# 12-DEBUG_JTAG.net
KiCad netlist of a schematic drawn in Altium Designer
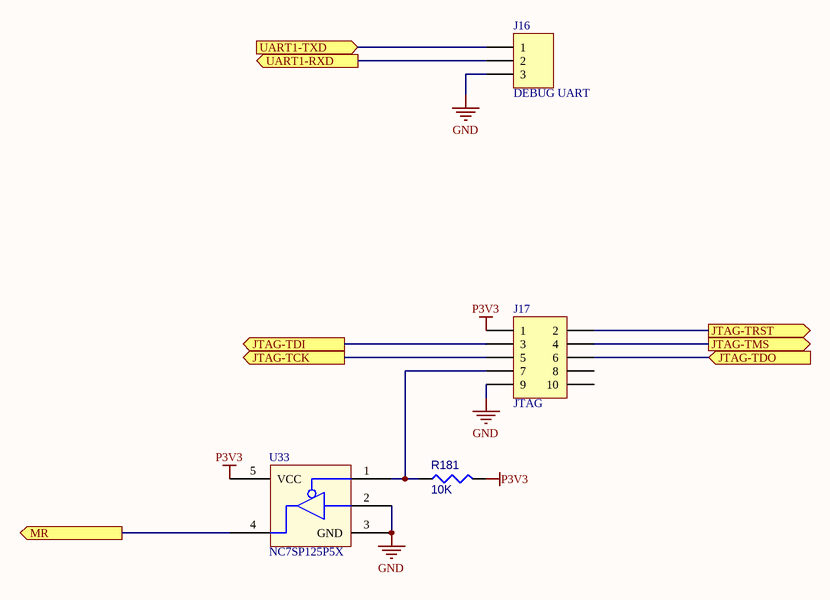
[diagram p0: 12-DEBUG_JTAG.SchDoc]

(export (version "E")
  (design (tool "Eeschema 10.0.6"))
  (components
    (comp (ref "J16")
      (value "DEBUG UART")
      (footprint "HDR1X3")
      (description "Header, 3-Pin")
      (fields (field (name "PUBLISHER") "Altium Limited"))
      (libsource (lib "Miscellaneous Connectors") (part "Header 3"))
    )
    (comp (ref "J17")
      (value "JTAG")
      (footprint "HDR2X5")
      (description "Header, 5-Pin, Dual row")
      (fields (field (name "PUBLISHER") "Altium Limited"))
      (libsource (lib "Miscellaneous Connectors") (part "Header 5X2"))
    )
    (comp (ref "R181") (value "10K") (footprint "0402") (libsource (lib "*") (part "P_R")))
    (comp (ref "U33")
      (value "NC7SP125P5X")
      (footprint "SC70")
      (libsource (lib "Schlib") (part "NC7SP125P5X"))
    )
  )
  (nets
    (net (code "1") (name "/JTAG-TCK") (class "Default")
      (node (ref "J17") (pin "5") (pinfunction "5_5") (pintype "passive"))
    )
    (net (code "2") (name "/JTAG-TDI") (class "Default")
      (node (ref "J17") (pin "3") (pinfunction "3_3") (pintype "passive"))
    )
    (net (code "3") (name "/JTAG-TDO") (class "Default")
      (node (ref "J17") (pin "6") (pinfunction "6_6") (pintype "passive"))
    )
    (net (code "4") (name "/JTAG-TMS") (class "Default")
      (node (ref "J17") (pin "4") (pinfunction "4_4") (pintype "passive"))
    )
    (net (code "5") (name "/JTAG-TRST") (class "Default")
      (node (ref "J17") (pin "2") (pinfunction "2_2") (pintype "passive"))
    )
    (net (code "6") (name "/MR") (class "Default")
      (node (ref "U33") (pin "4") (pinfunction "Y_4") (pintype "passive"))
    )
    (net (code "7") (name "/UART1-RXD") (class "Default")
      (node (ref "J16") (pin "2") (pinfunction "2_2") (pintype "passive"))
    )
    (net (code "8") (name "/UART1-TXD") (class "Default")
      (node (ref "J16") (pin "1") (pinfunction "1_1") (pintype "passive"))
    )
    (net (code "9") (name "GND") (class "Default")
      (node (ref "J16") (pin "3") (pinfunction "3_3") (pintype "passive"))
      (node (ref "J17") (pin "9") (pinfunction "9_9") (pintype "passive"))
      (node (ref "U33") (pin "2") (pinfunction "A_2") (pintype "passive"))
      (node (ref "U33") (pin "3") (pinfunction "GND_3") (pintype "passive"))
    )
    (net (code "10") (name "Net-(U33-OE)") (class "Default")
      (node (ref "J17") (pin "7") (pinfunction "7_7") (pintype "passive"))
      (node (ref "R181") (pin "2") (pinfunction "2_2") (pintype "passive"))
      (node (ref "U33") (pin "1") (pinfunction "OE_1") (pintype "passive"))
    )
    (net (code "11") (name "P3V3") (class "Default")
      (node (ref "J17") (pin "1") (pinfunction "1_1") (pintype "passive"))
      (node (ref "R181") (pin "1") (pinfunction "1_1") (pintype "passive"))
      (node (ref "U33") (pin "5") (pinfunction "VCC_5") (pintype "passive"))
    )
    (net (code "12") (name "unconnected-(J17-Pad8)") (class "Default")
      (node (ref "J17") (pin "8") (pinfunction "8_8") (pintype "passive"))
    )
    (net (code "13") (name "unconnected-(J17-Pad10)") (class "Default")
      (node (ref "J17") (pin "10") (pinfunction "10_10") (pintype "passive"))
    )
  )
)
